# ISPbreadboardAdapter_ATmega328compatible.net
KiCad netlist of a schematic drawn in EAGLE
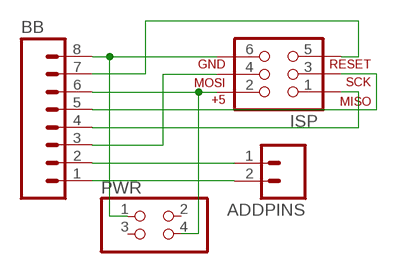
[diagram p0: schematic, sheet 1]

(export (version "E")
  (design (tool "Eeschema 10.0.6"))
  (components
    (comp (ref "ADDPINS")
      (value "M02PTH")
      (footprint "eagle-import:1X02")
      (libsource (lib "eagle-import") (part "M02PTH"))
    )
    (comp (ref "BB")
      (value "M08")
      (footprint "eagle-import:1X08_ROUND")
      (libsource (lib "eagle-import") (part "M08"))
    )
    (comp (ref "ISP")
      (value "AVR_SPI_PRG_6PTH")
      (footprint "eagle-import:2X3")
      (libsource (lib "eagle-import") (part "AVR_SPI_PRG_6PTH"))
    )
    (comp (ref "PWR")
      (value "PINHD-2X2")
      (footprint "eagle-import:2X02")
      (libsource (lib "eagle-import") (part "PINHD-2X2"))
    )
  )
  (nets
    (net (code "1") (name "Net-(ADDPINS-Pad1)") (class "Default")
      (node (ref "ADDPINS") (pin "1") (pinfunction "1_1") (pintype "passive"))
      (node (ref "BB") (pin "2") (pinfunction "2_2") (pintype "passive"))
    )
    (net (code "2") (name "Net-(ADDPINS-Pad2)") (class "Default")
      (node (ref "ADDPINS") (pin "2") (pinfunction "2_2") (pintype "passive"))
      (node (ref "BB") (pin "1") (pinfunction "1_1") (pintype "passive"))
    )
    (net (code "3") (name "Net-(BB-Pad3)") (class "Default")
      (node (ref "BB") (pin "3") (pinfunction "3_3") (pintype "passive"))
      (node (ref "ISP") (pin "4") (pinfunction "4_4") (pintype "passive"))
    )
    (net (code "4") (name "Net-(BB-Pad4)") (class "Default")
      (node (ref "BB") (pin "4") (pinfunction "4_4") (pintype "passive"))
      (node (ref "ISP") (pin "1") (pinfunction "1_1") (pintype "passive"))
    )
    (net (code "5") (name "Net-(BB-Pad5)") (class "Default")
      (node (ref "BB") (pin "5") (pinfunction "5_5") (pintype "passive"))
      (node (ref "ISP") (pin "3") (pinfunction "3_3") (pintype "passive"))
    )
    (net (code "6") (name "Net-(BB-Pad6)") (class "Default")
      (node (ref "BB") (pin "6") (pinfunction "6_6") (pintype "passive"))
      (node (ref "ISP") (pin "2") (pinfunction "2_2") (pintype "passive"))
      (node (ref "PWR") (pin "4") (pinfunction "4_4") (pintype "passive"))
    )
    (net (code "7") (name "Net-(BB-Pad7)") (class "Default")
      (node (ref "BB") (pin "7") (pinfunction "7_7") (pintype "passive"))
      (node (ref "ISP") (pin "5") (pinfunction "5_5") (pintype "passive"))
    )
    (net (code "8") (name "Net-(BB-Pad8)") (class "Default")
      (node (ref "BB") (pin "8") (pinfunction "8_8") (pintype "passive"))
      (node (ref "ISP") (pin "6") (pinfunction "6_6") (pintype "passive"))
      (node (ref "PWR") (pin "1") (pinfunction "1_1") (pintype "passive"))
    )
    (net (code "9") (name "unconnected-(PWR-Pad2)") (class "Default")
      (node (ref "PWR") (pin "2") (pinfunction "2_2") (pintype "passive"))
    )
    (net (code "10") (name "unconnected-(PWR-Pad3)") (class "Default")
      (node (ref "PWR") (pin "3") (pinfunction "3_3") (pintype "passive"))
    )
  )
)
